# FAL65816_Audio.net
KiCad netlist of a schematic drawn in EAGLE
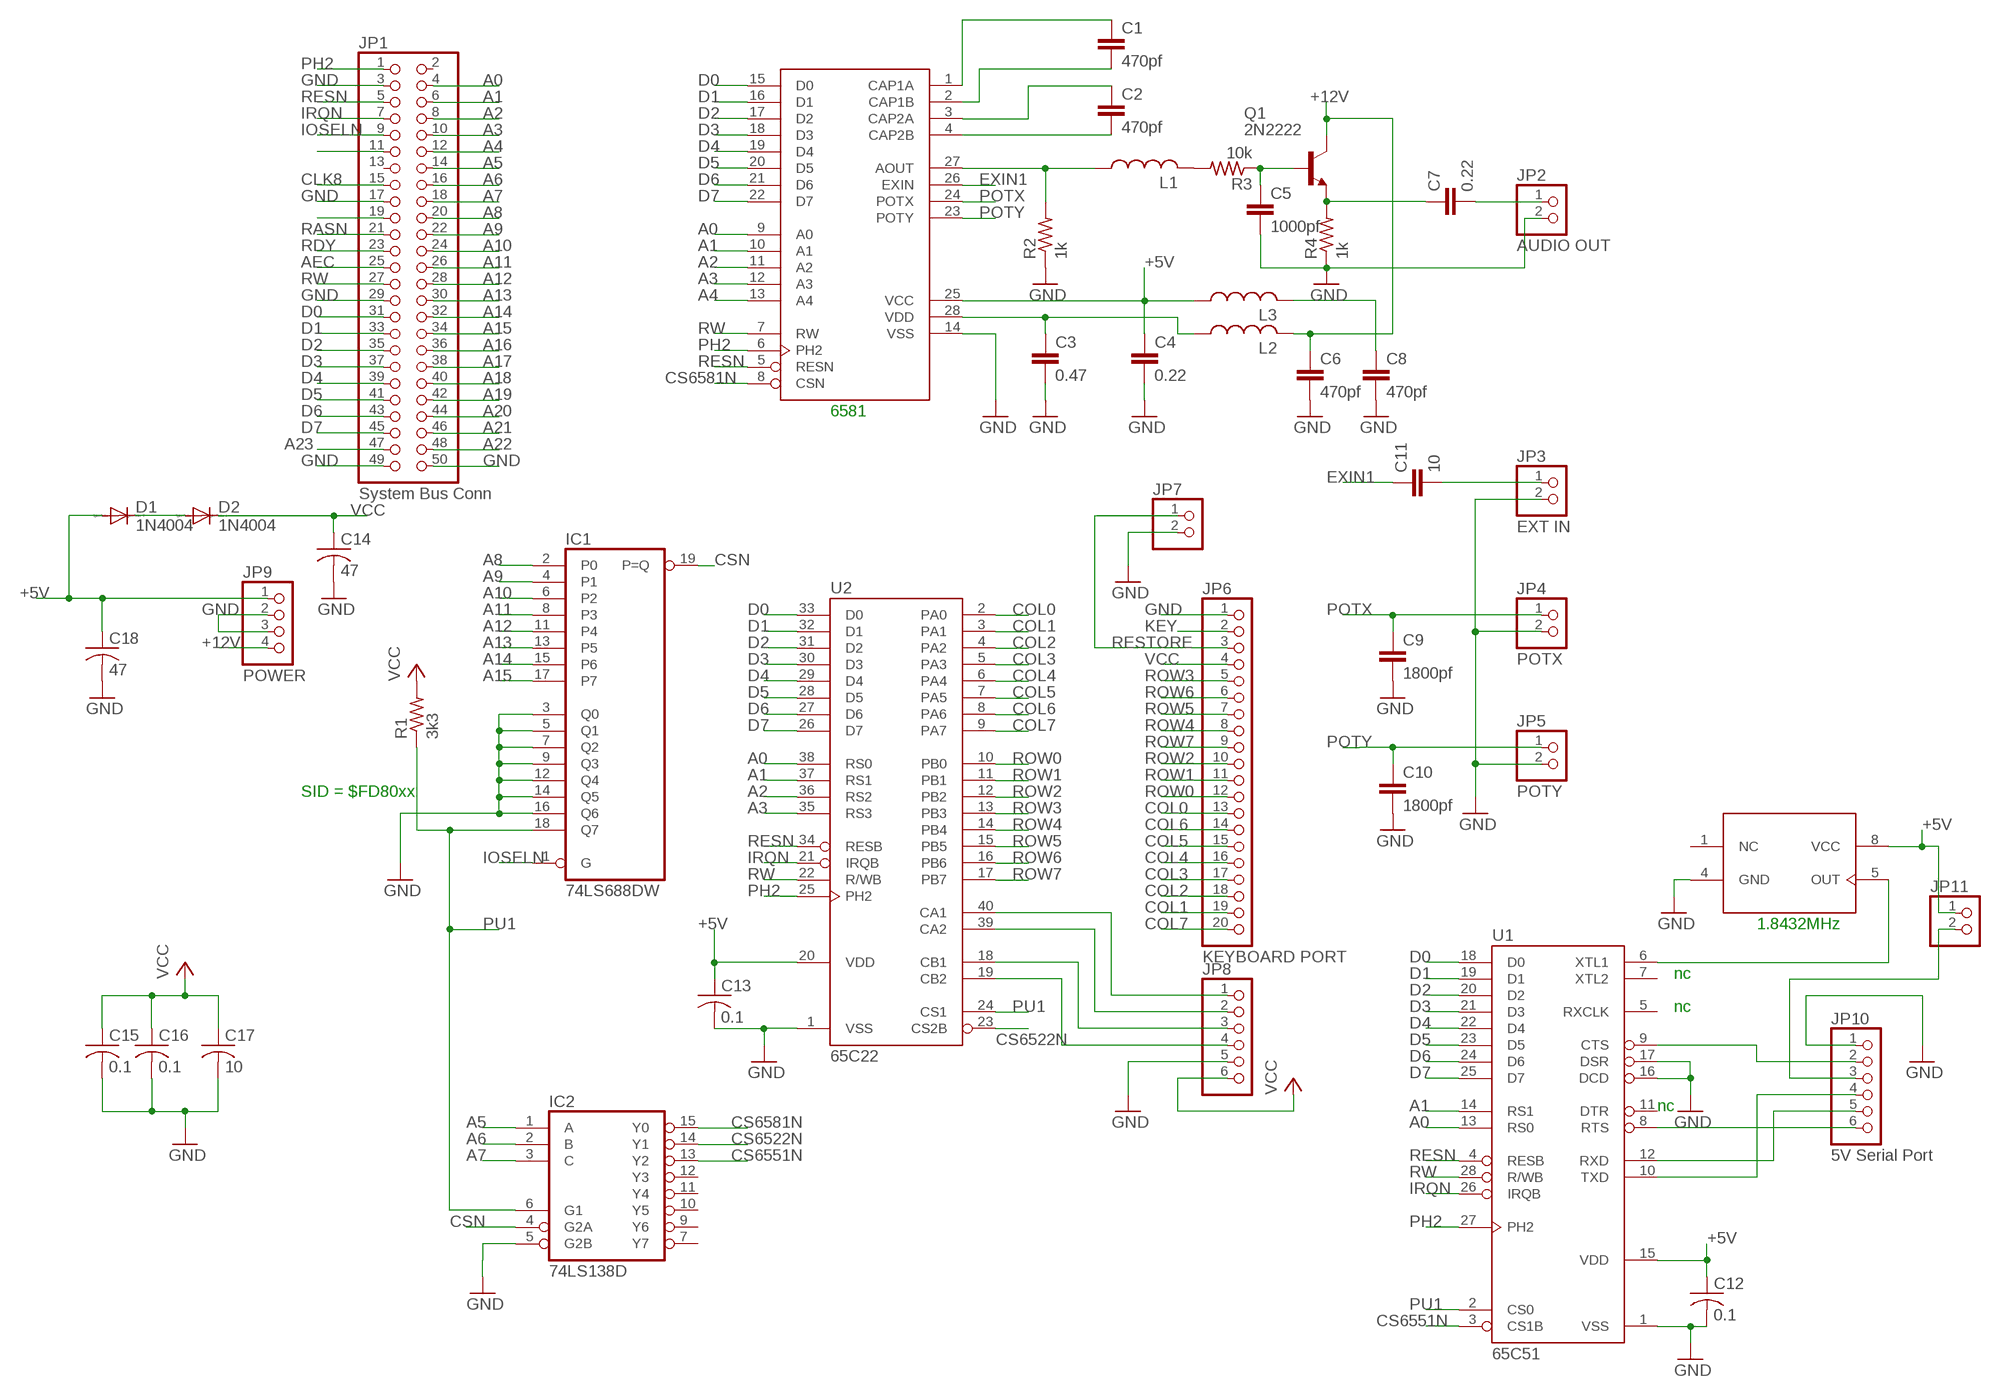
[diagram p0: schematic, sheet 1]

(export (version "E")
  (design (tool "Eeschema 10.0.6"))
  (components
    (comp (ref "C1")
      (value "470pf")
      (footprint "eagle-import:C050-024X044")
      (libsource (lib "eagle-import") (part "C-EU050-024X044"))
    )
    (comp (ref "C2")
      (value "470pf")
      (footprint "eagle-import:C050-024X044")
      (libsource (lib "eagle-import") (part "C-EU050-024X044"))
    )
    (comp (ref "C3")
      (value "0.47")
      (footprint "eagle-import:C050-024X044")
      (libsource (lib "eagle-import") (part "C-EU050-024X044"))
    )
    (comp (ref "C4")
      (value "0.22")
      (footprint "eagle-import:C050-024X044")
      (libsource (lib "eagle-import") (part "C-EU050-024X044"))
    )
    (comp (ref "C5")
      (value "1000pf")
      (footprint "eagle-import:C050-024X044")
      (libsource (lib "eagle-import") (part "C-EU050-024X044"))
    )
    (comp (ref "C6")
      (value "470pf")
      (footprint "eagle-import:C050-024X044")
      (libsource (lib "eagle-import") (part "C-EU050-024X044"))
    )
    (comp (ref "C7")
      (value "0.22")
      (footprint "eagle-import:C050-024X044")
      (libsource (lib "eagle-import") (part "C-EU050-024X044"))
    )
    (comp (ref "C8")
      (value "470pf")
      (footprint "eagle-import:C050-024X044")
      (libsource (lib "eagle-import") (part "C-EU050-024X044"))
    )
    (comp (ref "C9")
      (value "1800pf")
      (footprint "eagle-import:C050-024X044")
      (libsource (lib "eagle-import") (part "C-EU050-024X044"))
    )
    (comp (ref "C10")
      (value "1800pf")
      (footprint "eagle-import:C050-024X044")
      (libsource (lib "eagle-import") (part "C-EU050-024X044"))
    )
    (comp (ref "C11")
      (value "10")
      (footprint "eagle-import:C050-024X044")
      (libsource (lib "eagle-import") (part "C-EU050-024X044"))
    )
    (comp (ref "C12")
      (value "0.1")
      (footprint "eagle-import:C050-024X044")
      (libsource (lib "eagle-import") (part "C-US050-024X044"))
    )
    (comp (ref "C13")
      (value "0.1")
      (footprint "eagle-import:C050-024X044")
      (libsource (lib "eagle-import") (part "C-US050-024X044"))
    )
    (comp (ref "C14")
      (value "47")
      (footprint "eagle-import:C050-024X044")
      (libsource (lib "eagle-import") (part "C-US050-024X044"))
    )
    (comp (ref "C15")
      (value "0.1")
      (footprint "eagle-import:C050-024X044")
      (libsource (lib "eagle-import") (part "C-US050-024X044"))
    )
    (comp (ref "C16")
      (value "0.1")
      (footprint "eagle-import:C050-024X044")
      (libsource (lib "eagle-import") (part "C-US050-024X044"))
    )
    (comp (ref "C17")
      (value "10")
      (footprint "eagle-import:C050-024X044")
      (libsource (lib "eagle-import") (part "C-US050-024X044"))
    )
    (comp (ref "C18")
      (value "47")
      (footprint "eagle-import:C050-024X044")
      (libsource (lib "eagle-import") (part "C-US050-024X044"))
    )
    (comp (ref "D1")
      (value "1N4004")
      (footprint "eagle-import:DO41-10")
      (libsource (lib "eagle-import") (part "1N4004"))
    )
    (comp (ref "D2")
      (value "1N4004")
      (footprint "eagle-import:DO41-10")
      (libsource (lib "eagle-import") (part "1N4004"))
    )
    (comp (ref "IC1")
      (value "74LS688DW")
      (footprint "eagle-import:SO20W")
      (libsource (lib "eagle-import") (part "74688DWLS"))
    )
    (comp (ref "IC2")
      (value "74LS138D")
      (footprint "eagle-import:SO16")
      (libsource (lib "eagle-import") (part "74138DLS"))
    )
    (comp (ref "JP1")
      (value "System Bus Conn")
      (footprint "eagle-import:2X25_90")
      (libsource (lib "eagle-import") (part "PINHD-2X25/90"))
    )
    (comp (ref "JP2")
      (value "AUDIO OUT")
      (footprint "eagle-import:1X02")
      (libsource (lib "eagle-import") (part "PINHD-1X2"))
    )
    (comp (ref "JP3")
      (value "EXT IN")
      (footprint "eagle-import:1X02")
      (libsource (lib "eagle-import") (part "PINHD-1X2"))
    )
    (comp (ref "JP4")
      (value "POTX")
      (footprint "eagle-import:1X02")
      (libsource (lib "eagle-import") (part "PINHD-1X2"))
    )
    (comp (ref "JP5")
      (value "POTY")
      (footprint "eagle-import:1X02")
      (libsource (lib "eagle-import") (part "PINHD-1X2"))
    )
    (comp (ref "JP6")
      (value "KEYBOARD PORT")
      (footprint "eagle-import:1X20")
      (libsource (lib "eagle-import") (part "PINHD-1X20"))
    )
    (comp (ref "JP7")
      (value "PINHD-1X2")
      (footprint "eagle-import:1X02")
      (libsource (lib "eagle-import") (part "PINHD-1X2"))
    )
    (comp (ref "JP8")
      (value "PINHD-1X6/90")
      (footprint "eagle-import:1X06_90")
      (libsource (lib "eagle-import") (part "PINHD-1X6/90"))
    )
    (comp (ref "JP9")
      (value "POWER")
      (footprint "eagle-import:1X04_90")
      (libsource (lib "eagle-import") (part "PINHD-1X4/90"))
    )
    (comp (ref "JP10")
      (value "5V Serial Port")
      (footprint "eagle-import:1X06_90")
      (libsource (lib "eagle-import") (part "PINHD-1X6/90"))
    )
    (comp (ref "JP11")
      (value "PINHD-1X2")
      (footprint "eagle-import:1X02")
      (libsource (lib "eagle-import") (part "PINHD-1X2"))
    )
    (comp (ref "L1")
      (value "L-US0204/7")
      (footprint "eagle-import:0204_7")
      (libsource (lib "eagle-import") (part "L-US0204/7"))
    )
    (comp (ref "L2")
      (value "L-US0204/7")
      (footprint "eagle-import:0204_7")
      (libsource (lib "eagle-import") (part "L-US0204/7"))
    )
    (comp (ref "L3")
      (value "L-US0204/7")
      (footprint "eagle-import:0204_7")
      (libsource (lib "eagle-import") (part "L-US0204/7"))
    )
    (comp (ref "Q1")
      (value "2N2222")
      (footprint "eagle-import:TO18")
      (libsource (lib "eagle-import") (part "2N2222"))
    )
    (comp (ref "R1")
      (value "3k3")
      (footprint "eagle-import:0204_7")
      (libsource (lib "eagle-import") (part "R-US_0204/7"))
    )
    (comp (ref "R2")
      (value "1k")
      (footprint "eagle-import:0204_7")
      (libsource (lib "eagle-import") (part "R-US_0204/7"))
    )
    (comp (ref "R3")
      (value "10k")
      (footprint "eagle-import:0204_7")
      (libsource (lib "eagle-import") (part "R-US_0204/7"))
    )
    (comp (ref "R4")
      (value "1k")
      (footprint "eagle-import:0204_7")
      (libsource (lib "eagle-import") (part "R-US_0204/7"))
    )
    (comp (ref "U$1")
      (value "6581")
      (footprint "eagle-import:DIP-28")
      (libsource (lib "eagle-import") (part "FT6581"))
    )
    (comp (ref "U$2")
      (value "1.8432MHz")
      (footprint "eagle-import:DIL08")
      (libsource (lib "eagle-import") (part "OSC"))
    )
    (comp (ref "U1")
      (value "65C51")
      (footprint "eagle-import:DIP-28")
      (libsource (lib "eagle-import") (part "G65SC51P"))
    )
    (comp (ref "U2")
      (value "65C22")
      (footprint "eagle-import:DIP-40")
      (libsource (lib "eagle-import") (part "G65SC22P"))
    )
  )
  (nets
    (net (code "1") (name "/+5V") (class "Default")
      (node (ref "C12") (pin "1") (pinfunction "1_1") (pintype "passive"))
      (node (ref "C13") (pin "1") (pinfunction "1_1") (pintype "passive"))
      (node (ref "C18") (pin "1") (pinfunction "1_1") (pintype "passive"))
      (node (ref "C4") (pin "1") (pinfunction "1_1") (pintype "passive"))
      (node (ref "D1") (pin "A") (pinfunction "A_A") (pintype "passive"))
      (node (ref "JP11") (pin "1") (pinfunction "1_1") (pintype "passive"))
      (node (ref "JP9") (pin "1") (pinfunction "1_1") (pintype "passive"))
      (node (ref "L3") (pin "1") (pinfunction "1_1") (pintype "passive"))
      (node (ref "U$1") (pin "25") (pinfunction "VCC_25") (pintype "power_in"))
      (node (ref "U$2") (pin "8") (pinfunction "VCC_8") (pintype "power_in"))
      (node (ref "U1") (pin "15") (pinfunction "VDD_15") (pintype "power_in"))
      (node (ref "U2") (pin "20") (pinfunction "VDD_20") (pintype "power_in"))
    )
    (net (code "2") (name "/+12V") (class "Default")
      (node (ref "C6") (pin "1") (pinfunction "1_1") (pintype "passive"))
      (node (ref "JP9") (pin "4") (pinfunction "4_4") (pintype "passive"))
      (node (ref "L2") (pin "2") (pinfunction "2_2") (pintype "passive"))
      (node (ref "Q1") (pin "3") (pinfunction "C_3") (pintype "passive"))
    )
    (net (code "3") (name "/A0") (class "Default")
      (node (ref "JP1") (pin "4") (pinfunction "4_4") (pintype "passive"))
      (node (ref "U$1") (pin "9") (pinfunction "A0_9") (pintype "input"))
      (node (ref "U1") (pin "13") (pinfunction "RS0_13") (pintype "input"))
      (node (ref "U2") (pin "38") (pinfunction "RS0_38") (pintype "input"))
    )
    (net (code "4") (name "/A1") (class "Default")
      (node (ref "JP1") (pin "6") (pinfunction "6_6") (pintype "passive"))
      (node (ref "U$1") (pin "10") (pinfunction "A1_10") (pintype "input"))
      (node (ref "U1") (pin "14") (pinfunction "RS1_14") (pintype "input"))
      (node (ref "U2") (pin "37") (pinfunction "RS1_37") (pintype "input"))
    )
    (net (code "5") (name "/A2") (class "Default")
      (node (ref "JP1") (pin "8") (pinfunction "8_8") (pintype "passive"))
      (node (ref "U$1") (pin "11") (pinfunction "A2_11") (pintype "input"))
      (node (ref "U2") (pin "36") (pinfunction "RS2_36") (pintype "input"))
    )
    (net (code "6") (name "/A3") (class "Default")
      (node (ref "JP1") (pin "10") (pinfunction "10_10") (pintype "passive"))
      (node (ref "U$1") (pin "12") (pinfunction "A3_12") (pintype "input"))
      (node (ref "U2") (pin "35") (pinfunction "RS3_35") (pintype "input"))
    )
    (net (code "7") (name "/A4") (class "Default")
      (node (ref "JP1") (pin "12") (pinfunction "12_12") (pintype "passive"))
      (node (ref "U$1") (pin "13") (pinfunction "A4_13") (pintype "input"))
    )
    (net (code "8") (name "/A5") (class "Default")
      (node (ref "IC2") (pin "1") (pinfunction "A_1") (pintype "input"))
      (node (ref "JP1") (pin "14") (pinfunction "14_14") (pintype "passive"))
    )
    (net (code "9") (name "/A6") (class "Default")
      (node (ref "IC2") (pin "2") (pinfunction "B_2") (pintype "input"))
      (node (ref "JP1") (pin "16") (pinfunction "16_16") (pintype "passive"))
    )
    (net (code "10") (name "/A7") (class "Default")
      (node (ref "IC2") (pin "3") (pinfunction "C_3") (pintype "input"))
      (node (ref "JP1") (pin "18") (pinfunction "18_18") (pintype "passive"))
    )
    (net (code "11") (name "/A8") (class "Default")
      (node (ref "IC1") (pin "2") (pinfunction "P0_2") (pintype "input"))
      (node (ref "JP1") (pin "20") (pinfunction "20_20") (pintype "passive"))
    )
    (net (code "12") (name "/A9") (class "Default")
      (node (ref "IC1") (pin "4") (pinfunction "P1_4") (pintype "input"))
      (node (ref "JP1") (pin "22") (pinfunction "22_22") (pintype "passive"))
    )
    (net (code "13") (name "/A10") (class "Default")
      (node (ref "IC1") (pin "6") (pinfunction "P2_6") (pintype "input"))
      (node (ref "JP1") (pin "24") (pinfunction "24_24") (pintype "passive"))
    )
    (net (code "14") (name "/A11") (class "Default")
      (node (ref "IC1") (pin "8") (pinfunction "P3_8") (pintype "input"))
      (node (ref "JP1") (pin "26") (pinfunction "26_26") (pintype "passive"))
    )
    (net (code "15") (name "/A12") (class "Default")
      (node (ref "IC1") (pin "11") (pinfunction "P4_11") (pintype "input"))
      (node (ref "JP1") (pin "28") (pinfunction "28_28") (pintype "passive"))
    )
    (net (code "16") (name "/A13") (class "Default")
      (node (ref "IC1") (pin "13") (pinfunction "P5_13") (pintype "input"))
      (node (ref "JP1") (pin "30") (pinfunction "30_30") (pintype "passive"))
    )
    (net (code "17") (name "/A14") (class "Default")
      (node (ref "IC1") (pin "15") (pinfunction "P6_15") (pintype "input"))
      (node (ref "JP1") (pin "32") (pinfunction "32_32") (pintype "passive"))
    )
    (net (code "18") (name "/A15") (class "Default")
      (node (ref "IC1") (pin "17") (pinfunction "P7_17") (pintype "input"))
      (node (ref "JP1") (pin "34") (pinfunction "34_34") (pintype "passive"))
    )
    (net (code "19") (name "/A16") (class "Default")
      (node (ref "JP1") (pin "36") (pinfunction "36_36") (pintype "passive"))
    )
    (net (code "20") (name "/A17") (class "Default")
      (node (ref "JP1") (pin "38") (pinfunction "38_38") (pintype "passive"))
    )
    (net (code "21") (name "/A18") (class "Default")
      (node (ref "JP1") (pin "40") (pinfunction "40_40") (pintype "passive"))
    )
    (net (code "22") (name "/A19") (class "Default")
      (node (ref "JP1") (pin "42") (pinfunction "42_42") (pintype "passive"))
    )
    (net (code "23") (name "/A20") (class "Default")
      (node (ref "JP1") (pin "44") (pinfunction "44_44") (pintype "passive"))
    )
    (net (code "24") (name "/A21") (class "Default")
      (node (ref "JP1") (pin "46") (pinfunction "46_46") (pintype "passive"))
    )
    (net (code "25") (name "/A22") (class "Default")
      (node (ref "JP1") (pin "48") (pinfunction "48_48") (pintype "passive"))
    )
    (net (code "26") (name "/A23") (class "Default")
      (node (ref "JP1") (pin "47") (pinfunction "47_47") (pintype "passive"))
    )
    (net (code "27") (name "/AEC") (class "Default")
      (node (ref "JP1") (pin "25") (pinfunction "25_25") (pintype "passive"))
    )
    (net (code "28") (name "/CLK8") (class "Default")
      (node (ref "JP1") (pin "15") (pinfunction "15_15") (pintype "passive"))
    )
    (net (code "29") (name "/COL0") (class "Default")
      (node (ref "JP6") (pin "13") (pinfunction "13_13") (pintype "passive"))
      (node (ref "U2") (pin "2") (pinfunction "PA0_2") (pintype "bidirectional"))
    )
    (net (code "30") (name "/COL1") (class "Default")
      (node (ref "JP6") (pin "19") (pinfunction "19_19") (pintype "passive"))
      (node (ref "U2") (pin "3") (pinfunction "PA1_3") (pintype "bidirectional"))
    )
    (net (code "31") (name "/COL2") (class "Default")
      (node (ref "JP6") (pin "18") (pinfunction "18_18") (pintype "passive"))
      (node (ref "U2") (pin "4") (pinfunction "PA2_4") (pintype "bidirectional"))
    )
    (net (code "32") (name "/COL3") (class "Default")
      (node (ref "JP6") (pin "17") (pinfunction "17_17") (pintype "passive"))
      (node (ref "U2") (pin "5") (pinfunction "PA3_5") (pintype "bidirectional"))
    )
    (net (code "33") (name "/COL4") (class "Default")
      (node (ref "JP6") (pin "16") (pinfunction "16_16") (pintype "passive"))
      (node (ref "U2") (pin "6") (pinfunction "PA4_6") (pintype "bidirectional"))
    )
    (net (code "34") (name "/COL5") (class "Default")
      (node (ref "JP6") (pin "15") (pinfunction "15_15") (pintype "passive"))
      (node (ref "U2") (pin "7") (pinfunction "PA5_7") (pintype "bidirectional"))
    )
    (net (code "35") (name "/COL6") (class "Default")
      (node (ref "JP6") (pin "14") (pinfunction "14_14") (pintype "passive"))
      (node (ref "U2") (pin "8") (pinfunction "PA6_8") (pintype "bidirectional"))
    )
    (net (code "36") (name "/COL7") (class "Default")
      (node (ref "JP6") (pin "20") (pinfunction "20_20") (pintype "passive"))
      (node (ref "U2") (pin "9") (pinfunction "PA7_9") (pintype "bidirectional"))
    )
    (net (code "37") (name "/CS6522N") (class "Default")
      (node (ref "IC2") (pin "14") (pinfunction "Y1_14") (pintype "output"))
      (node (ref "U2") (pin "23") (pinfunction "CS2B_23") (pintype "input"))
    )
    (net (code "38") (name "/CS6551N") (class "Default")
      (node (ref "IC2") (pin "13") (pinfunction "Y2_13") (pintype "output"))
      (node (ref "U1") (pin "3") (pinfunction "CS1B_3") (pintype "input"))
    )
    (net (code "39") (name "/CS6581N") (class "Default")
      (node (ref "IC2") (pin "15") (pinfunction "Y0_15") (pintype "output"))
      (node (ref "U$1") (pin "8") (pinfunction "CSN_8") (pintype "input"))
    )
    (net (code "40") (name "/CSN") (class "Default")
      (node (ref "IC1") (pin "19") (pinfunction "P=Q_19") (pintype "output"))
      (node (ref "IC2") (pin "4") (pinfunction "G2A_4") (pintype "input"))
    )
    (net (code "41") (name "/D0") (class "Default")
      (node (ref "JP1") (pin "31") (pinfunction "31_31") (pintype "passive"))
      (node (ref "U$1") (pin "15") (pinfunction "D0_15") (pintype "bidirectional"))
      (node (ref "U1") (pin "18") (pinfunction "D0_18") (pintype "bidirectional"))
      (node (ref "U2") (pin "33") (pinfunction "D0_33") (pintype "bidirectional"))
    )
    (net (code "42") (name "/D1") (class "Default")
      (node (ref "JP1") (pin "33") (pinfunction "33_33") (pintype "passive"))
      (node (ref "U$1") (pin "16") (pinfunction "D1_16") (pintype "bidirectional"))
      (node (ref "U1") (pin "19") (pinfunction "D1_19") (pintype "bidirectional"))
      (node (ref "U2") (pin "32") (pinfunction "D1_32") (pintype "bidirectional"))
    )
    (net (code "43") (name "/D2") (class "Default")
      (node (ref "JP1") (pin "35") (pinfunction "35_35") (pintype "passive"))
      (node (ref "U$1") (pin "17") (pinfunction "D2_17") (pintype "bidirectional"))
      (node (ref "U1") (pin "20") (pinfunction "D2_20") (pintype "bidirectional"))
      (node (ref "U2") (pin "31") (pinfunction "D2_31") (pintype "bidirectional"))
    )
    (net (code "44") (name "/D3") (class "Default")
      (node (ref "JP1") (pin "37") (pinfunction "37_37") (pintype "passive"))
      (node (ref "U$1") (pin "18") (pinfunction "D3_18") (pintype "bidirectional"))
      (node (ref "U1") (pin "21") (pinfunction "D3_21") (pintype "bidirectional"))
      (node (ref "U2") (pin "30") (pinfunction "D3_30") (pintype "bidirectional"))
    )
    (net (code "45") (name "/D4") (class "Default")
      (node (ref "JP1") (pin "39") (pinfunction "39_39") (pintype "passive"))
      (node (ref "U$1") (pin "19") (pinfunction "D4_19") (pintype "bidirectional"))
      (node (ref "U1") (pin "22") (pinfunction "D4_22") (pintype "bidirectional"))
      (node (ref "U2") (pin "29") (pinfunction "D4_29") (pintype "bidirectional"))
    )
    (net (code "46") (name "/D5") (class "Default")
      (node (ref "JP1") (pin "41") (pinfunction "41_41") (pintype "passive"))
      (node (ref "U$1") (pin "20") (pinfunction "D5_20") (pintype "bidirectional"))
      (node (ref "U1") (pin "23") (pinfunction "D5_23") (pintype "bidirectional"))
      (node (ref "U2") (pin "28") (pinfunction "D5_28") (pintype "bidirectional"))
    )
    (net (code "47") (name "/D6") (class "Default")
      (node (ref "JP1") (pin "43") (pinfunction "43_43") (pintype "passive"))
      (node (ref "U$1") (pin "21") (pinfunction "D6_21") (pintype "bidirectional"))
      (node (ref "U1") (pin "24") (pinfunction "D6_24") (pintype "bidirectional"))
      (node (ref "U2") (pin "27") (pinfunction "D6_27") (pintype "bidirectional"))
    )
    (net (code "48") (name "/D7") (class "Default")
      (node (ref "JP1") (pin "45") (pinfunction "45_45") (pintype "passive"))
      (node (ref "U$1") (pin "22") (pinfunction "D7_22") (pintype "bidirectional"))
      (node (ref "U1") (pin "25") (pinfunction "D7_25") (pintype "bidirectional"))
      (node (ref "U2") (pin "26") (pinfunction "D7_26") (pintype "bidirectional"))
    )
    (net (code "49") (name "/EXIN1") (class "Default")
      (node (ref "C11") (pin "1") (pinfunction "1_1") (pintype "passive"))
      (node (ref "U$1") (pin "26") (pinfunction "EXIN_26") (pintype "input"))
    )
    (net (code "50") (name "/IOSELN") (class "Default")
      (node (ref "IC1") (pin "1") (pinfunction "G_1") (pintype "input"))
      (node (ref "JP1") (pin "9") (pinfunction "9_9") (pintype "passive"))
    )
    (net (code "51") (name "/IRQN") (class "Default")
      (node (ref "JP1") (pin "7") (pinfunction "7_7") (pintype "passive"))
      (node (ref "U1") (pin "26") (pinfunction "IRQB_26") (pintype "output"))
      (node (ref "U2") (pin "21") (pinfunction "IRQB_21") (pintype "output"))
    )
    (net (code "52") (name "/KEY") (class "Default")
      (node (ref "JP6") (pin "2") (pinfunction "2_2") (pintype "passive"))
    )
    (net (code "53") (name "/PH2") (class "Default")
      (node (ref "JP1") (pin "1") (pinfunction "1_1") (pintype "passive"))
      (node (ref "U$1") (pin "6") (pinfunction "PH2_6") (pintype "input"))
      (node (ref "U1") (pin "27") (pinfunction "PH2_27") (pintype "power_in"))
      (node (ref "U2") (pin "25") (pinfunction "PH2_25") (pintype "input"))
    )
    (net (code "54") (name "/POTX") (class "Default")
      (node (ref "C9") (pin "1") (pinfunction "1_1") (pintype "passive"))
      (node (ref "JP4") (pin "1") (pinfunction "1_1") (pintype "passive"))
      (node (ref "U$1") (pin "24") (pinfunction "POTX_24") (pintype "input"))
    )
    (net (code "55") (name "/POTY") (class "Default")
      (node (ref "C10") (pin "1") (pinfunction "1_1") (pintype "passive"))
      (node (ref "JP5") (pin "1") (pinfunction "1_1") (pintype "passive"))
      (node (ref "U$1") (pin "23") (pinfunction "POTY_23") (pintype "input"))
    )
    (net (code "56") (name "/PU1") (class "Default")
      (node (ref "IC1") (pin "18") (pinfunction "Q7_18") (pintype "input"))
      (node (ref "IC2") (pin "6") (pinfunction "G1_6") (pintype "input"))
      (node (ref "R1") (pin "1") (pinfunction "1_1") (pintype "passive"))
      (node (ref "U1") (pin "2") (pinfunction "CS0_2") (pintype "input"))
      (node (ref "U2") (pin "24") (pinfunction "CS1_24") (pintype "input"))
    )
    (net (code "57") (name "/RASN") (class "Default")
      (node (ref "JP1") (pin "21") (pinfunction "21_21") (pintype "passive"))
    )
    (net (code "58") (name "/RDY") (class "Default")
      (node (ref "JP1") (pin "23") (pinfunction "23_23") (pintype "passive"))
    )
    (net (code "59") (name "/RESN") (class "Default")
      (node (ref "JP1") (pin "5") (pinfunction "5_5") (pintype "passive"))
      (node (ref "U$1") (pin "5") (pinfunction "RESN_5") (pintype "input"))
      (node (ref "U1") (pin "4") (pinfunction "RESB_4") (pintype "input"))
      (node (ref "U2") (pin "34") (pinfunction "RESB_34") (pintype "input"))
    )
    (net (code "60") (name "/RESTORE") (class "Default")
      (node (ref "JP6") (pin "3") (pinfunction "3_3") (pintype "passive"))
      (node (ref "JP7") (pin "1") (pinfunction "1_1") (pintype "passive"))
    )
    (net (code "61") (name "/ROW0") (class "Default")
      (node (ref "JP6") (pin "12") (pinfunction "12_12") (pintype "passive"))
      (node (ref "U2") (pin "10") (pinfunction "PB0_10") (pintype "bidirectional"))
    )
    (net (code "62") (name "/ROW1") (class "Default")
      (node (ref "JP6") (pin "11") (pinfunction "11_11") (pintype "passive"))
      (node (ref "U2") (pin "11") (pinfunction "PB1_11") (pintype "bidirectional"))
    )
    (net (code "63") (name "/ROW2") (class "Default")
      (node (ref "JP6") (pin "10") (pinfunction "10_10") (pintype "passive"))
      (node (ref "U2") (pin "12") (pinfunction "PB2_12") (pintype "bidirectional"))
    )
    (net (code "64") (name "/ROW3") (class "Default")
      (node (ref "JP6") (pin "5") (pinfunction "5_5") (pintype "passive"))
      (node (ref "U2") (pin "13") (pinfunction "PB3_13") (pintype "bidirectional"))
    )
    (net (code "65") (name "/ROW4") (class "Default")
      (node (ref "JP6") (pin "8") (pinfunction "8_8") (pintype "passive"))
      (node (ref "U2") (pin "14") (pinfunction "PB4_14") (pintype "bidirectional"))
    )
    (net (code "66") (name "/ROW5") (class "Default")
      (node (ref "JP6") (pin "7") (pinfunction "7_7") (pintype "passive"))
      (node (ref "U2") (pin "15") (pinfunction "PB5_15") (pintype "bidirectional"))
    )
    (net (code "67") (name "/ROW6") (class "Default")
      (node (ref "JP6") (pin "6") (pinfunction "6_6") (pintype "passive"))
      (node (ref "U2") (pin "16") (pinfunction "PB6_16") (pintype "bidirectional"))
    )
    (net (code "68") (name "/ROW7") (class "Default")
      (node (ref "JP6") (pin "9") (pinfunction "9_9") (pintype "passive"))
      (node (ref "U2") (pin "17") (pinfunction "PB7_17") (pintype "bidirectional"))
    )
    (net (code "69") (name "/RW") (class "Default")
      (node (ref "JP1") (pin "27") (pinfunction "27_27") (pintype "passive"))
      (node (ref "U$1") (pin "7") (pinfunction "RW_7") (pintype "input"))
      (node (ref "U1") (pin "28") (pinfunction "R/WB_28") (pintype "input"))
      (node (ref "U2") (pin "22") (pinfunction "R/WB_22") (pintype "input"))
    )
    (net (code "70") (name "GND") (class "Default")
      (node (ref "C10") (pin "2") (pinfunction "2_2") (pintype "passive"))
      (node (ref "C12") (pin "2") (pinfunction "2_2") (pintype "passive"))
      (node (ref "C13") (pin "2") (pinfunction "2_2") (pintype "passive"))
      (node (ref "C14") (pin "2") (pinfunction "2_2") (pintype "passive"))
      (node (ref "C15") (pin "2") (pinfunction "2_2") (pintype "passive"))
      (node (ref "C16") (pin "2") (pinfunction "2_2") (pintype "passive"))
      (node (ref "C17") (pin "2") (pinfunction "2_2") (pintype "passive"))
      (node (ref "C18") (pin "2") (pinfunction "2_2") (pintype "passive"))
      (node (ref "C3") (pin "2") (pinfunction "2_2") (pintype "passive"))
      (node (ref "C4") (pin "2") (pinfunction "2_2") (pintype "passive"))
      (node (ref "C5") (pin "2") (pinfunction "2_2") (pintype "passive"))
      (node (ref "C6") (pin "2") (pinfunction "2_2") (pintype "passive"))
      (node (ref "C8") (pin "2") (pinfunction "2_2") (pintype "passive"))
      (node (ref "C9") (pin "2") (pinfunction "2_2") (pintype "passive"))
      (node (ref "IC1") (pin "12") (pinfunction "Q4_12") (pintype "input"))
      (node (ref "IC1") (pin "14") (pinfunction "Q5_14") (pintype "input"))
      (node (ref "IC1") (pin "16") (pinfunction "Q6_16") (pintype "input"))
      (node (ref "IC1") (pin "3") (pinfunction "Q0_3") (pintype "input"))
      (node (ref "IC1") (pin "5") (pinfunction "Q1_5") (pintype "input"))
      (node (ref "IC1") (pin "7") (pinfunction "Q2_7") (pintype "input"))
      (node (ref "IC1") (pin "9") (pinfunction "Q3_9") (pintype "input"))
      (node (ref "IC2") (pin "5") (pinfunction "G2B_5") (pintype "input"))
      (node (ref "JP1") (pin "17") (pinfunction "17_17") (pintype "passive"))
      (node (ref "JP1") (pin "29") (pinfunction "29_29") (pintype "passive"))
      (node (ref "JP1") (pin "3") (pinfunction "3_3") (pintype "passive"))
      (node (ref "JP1") (pin "49") (pinfunction "49_49") (pintype "passive"))
      (node (ref "JP1") (pin "50") (pinfunction "50_50") (pintype "passive"))
      (node (ref "JP10") (pin "1") (pinfunction "1_1") (pintype "passive"))
      (node (ref "JP2") (pin "2") (pinfunction "2_2") (pintype "passive"))
      (node (ref "JP3") (pin "2") (pinfunction "2_2") (pintype "passive"))
      (node (ref "JP4") (pin "2") (pinfunction "2_2") (pintype "passive"))
      (node (ref "JP5") (pin "2") (pinfunction "2_2") (pintype "passive"))
      (node (ref "JP6") (pin "1") (pinfunction "1_1") (pintype "passive"))
      (node (ref "JP7") (pin "2") (pinfunction "2_2") (pintype "passive"))
      (node (ref "JP8") (pin "5") (pinfunction "5_5") (pintype "passive"))
      (node (ref "JP9") (pin "2") (pinfunction "2_2") (pintype "passive"))
      (node (ref "JP9") (pin "3") (pinfunction "3_3") (pintype "passive"))
      (node (ref "R2") (pin "1") (pinfunction "1_1") (pintype "passive"))
      (node (ref "R4") (pin "1") (pinfunction "1_1") (pintype "passive"))
      (node (ref "U$1") (pin "14") (pinfunction "VSS_14") (pintype "power_in"))
      (node (ref "U$2") (pin "4") (pinfunction "GND_4") (pintype "power_in"))
      (node (ref "U1") (pin "1") (pinfunction "VSS_1") (pintype "power_in"))
      (node (ref "U1") (pin "16") (pinfunction "DCD_16") (pintype "input"))
      (node (ref "U1") (pin "17") (pinfunction "DSR_17") (pintype "input"))
      (node (ref "U2") (pin "1") (pinfunction "VSS_1") (pintype "power_in"))
    )
    (net (code "71") (name "Net-(C7-Pad2)") (class "Default")
      (node (ref "C7") (pin "2") (pinfunction "2_2") (pintype "passive"))
      (node (ref "JP2") (pin "1") (pinfunction "1_1") (pintype "passive"))
    )
    (net (code "72") (name "Net-(C8-Pad1)") (class "Default")
      (node (ref "C8") (pin "1") (pinfunction "1_1") (pintype "passive"))
      (node (ref "L3") (pin "2") (pinfunction "2_2") (pintype "passive"))
    )
    (net (code "73") (name "Net-(C11-Pad2)") (class "Default")
      (node (ref "C11") (pin "2") (pinfunction "2_2") (pintype "passive"))
      (node (ref "JP3") (pin "1") (pinfunction "1_1") (pintype "passive"))
    )
    (net (code "74") (name "Net-(D1-PadC)") (class "Default")
      (node (ref "D1") (pin "C") (pinfunction "C_C") (pintype "passive"))
      (node (ref "D2") (pin "A") (pinfunction "A_A") (pintype "passive"))
    )
    (net (code "75") (name "Net-(JP10-Pad3)") (class "Default")
      (node (ref "JP10") (pin "3") (pinfunction "3_3") (pintype "passive"))
      (node (ref "JP11") (pin "2") (pinfunction "2_2") (pintype "passive"))
    )
    (net (code "76") (name "Net-(L1-Pad2)") (class "Default")
      (node (ref "L1") (pin "2") (pinfunction "2_2") (pintype "passive"))
      (node (ref "R3") (pin "2") (pinfunction "2_2") (pintype "passive"))
    )
    (net (code "77") (name "Net-(Q1-B)") (class "Default")
      (node (ref "C5") (pin "1") (pinfunction "1_1") (pintype "passive"))
      (node (ref "Q1") (pin "2") (pinfunction "B_2") (pintype "passive"))
      (node (ref "R3") (pin "1") (pinfunction "1_1") (pintype "passive"))
    )
    (net (code "78") (name "Net-(Q1-E)") (class "Default")
      (node (ref "C7") (pin "1") (pinfunction "1_1") (pintype "passive"))
      (node (ref "Q1") (pin "1") (pinfunction "E_1") (pintype "passive"))
      (node (ref "R4") (pin "2") (pinfunction "2_2") (pintype "passive"))
    )
    (net (code "79") (name "Net-(U$1-AOUT)") (class "Default")
      (node (ref "L1") (pin "1") (pinfunction "1_1") (pintype "passive"))
      (node (ref "R2") (pin "2") (pinfunction "2_2") (pintype "passive"))
      (node (ref "U$1") (pin "27") (pinfunction "AOUT_27") (pintype "output"))
    )
    (net (code "80") (name "Net-(U$1-CAP1A)") (class "Default")
      (node (ref "C1") (pin "1") (pinfunction "1_1") (pintype "passive"))
      (node (ref "U$1") (pin "1") (pinfunction "CAP1A_1") (pintype "bidirectional"))
    )
    (net (code "81") (name "Net-(U$1-CAP1B)") (class "Default")
      (node (ref "C1") (pin "2") (pinfunction "2_2") (pintype "passive"))
      (node (ref "U$1") (pin "2") (pinfunction "CAP1B_2") (pintype "bidirectional"))
    )
    (net (code "82") (name "Net-(U$1-CAP2A)") (class "Default")
      (node (ref "C2") (pin "1") (pinfunction "1_1") (pintype "passive"))
      (node (ref "U$1") (pin "3") (pinfunction "CAP2A_3") (pintype "bidirectional"))
    )
    (net (code "83") (name "Net-(U$1-CAP2B)") (class "Default")
      (node (ref "C2") (pin "2") (pinfunction "2_2") (pintype "passive"))
      (node (ref "U$1") (pin "4") (pinfunction "CAP2B_4") (pintype "bidirectional"))
    )
    (net (code "84") (name "Net-(U$1-VDD)") (class "Default")
      (node (ref "C3") (pin "1") (pinfunction "1_1") (pintype "passive"))
      (node (ref "L2") (pin "1") (pinfunction "1_1") (pintype "passive"))
      (node (ref "U$1") (pin "28") (pinfunction "VDD_28") (pintype "power_in"))
    )
    (net (code "85") (name "Net-(U$2-OUT)") (class "Default")
      (node (ref "U$2") (pin "5") (pinfunction "OUT_5") (pintype "output"))
      (node (ref "U1") (pin "6") (pinfunction "XTL1_6") (pintype "input"))
    )
    (net (code "86") (name "Net-(U1-CTS)") (class "Default")
      (node (ref "JP10") (pin "2") (pinfunction "2_2") (pintype "passive"))
      (node (ref "U1") (pin "9") (pinfunction "CTS_9") (pintype "input"))
    )
    (net (code "87") (name "Net-(U1-RTS)") (class "Default")
      (node (ref "JP10") (pin "6") (pinfunction "6_6") (pintype "passive"))
      (node (ref "U1") (pin "8") (pinfunction "RTS_8") (pintype "output"))
    )
    (net (code "88") (name "Net-(U1-RXD)") (class "Default")
      (node (ref "JP10") (pin "5") (pinfunction "5_5") (pintype "passive"))
      (node (ref "U1") (pin "12") (pinfunction "RXD_12") (pintype "input"))
    )
    (net (code "89") (name "Net-(U1-TXD)") (class "Default")
      (node (ref "JP10") (pin "4") (pinfunction "4_4") (pintype "passive"))
      (node (ref "U1") (pin "10") (pinfunction "TXD_10") (pintype "output"))
    )
    (net (code "90") (name "Net-(U2-CA1)") (class "Default")
      (node (ref "JP8") (pin "1") (pinfunction "1_1") (pintype "passive"))
      (node (ref "U2") (pin "40") (pinfunction "CA1_40") (pintype "bidirectional"))
    )
    (net (code "91") (name "Net-(U2-CA2)") (class "Default")
      (node (ref "JP8") (pin "2") (pinfunction "2_2") (pintype "passive"))
      (node (ref "U2") (pin "39") (pinfunction "CA2_39") (pintype "bidirectional"))
    )
    (net (code "92") (name "Net-(U2-CB1)") (class "Default")
      (node (ref "JP8") (pin "3") (pinfunction "3_3") (pintype "passive"))
      (node (ref "U2") (pin "18") (pinfunction "CB1_18") (pintype "bidirectional"))
    )
    (net (code "93") (name "Net-(U2-CB2)") (class "Default")
      (node (ref "JP8") (pin "4") (pinfunction "4_4") (pintype "passive"))
      (node (ref "U2") (pin "19") (pinfunction "CB2_19") (pintype "bidirectional"))
    )
    (net (code "94") (name "VCC") (class "Default")
      (node (ref "C14") (pin "1") (pinfunction "1_1") (pintype "passive"))
      (node (ref "C15") (pin "1") (pinfunction "1_1") (pintype "passive"))
      (node (ref "C16") (pin "1") (pinfunction "1_1") (pintype "passive"))
      (node (ref "C17") (pin "1") (pinfunction "1_1") (pintype "passive"))
      (node (ref "D2") (pin "C") (pinfunction "C_C") (pintype "passive"))
      (node (ref "JP6") (pin "4") (pinfunction "4_4") (pintype "passive"))
      (node (ref "JP8") (pin "6") (pinfunction "6_6") (pintype "passive"))
      (node (ref "R1") (pin "2") (pinfunction "2_2") (pintype "passive"))
    )
    (net (code "95") (name "unconnected-(IC2A-Y3-Pad12)") (class "Default")
      (node (ref "IC2") (pin "12") (pinfunction "Y3_12") (pintype "output"))
    )
    (net (code "96") (name "unconnected-(IC2A-Y4-Pad11)") (class "Default")
      (node (ref "IC2") (pin "11") (pinfunction "Y4_11") (pintype "output"))
    )
    (net (code "97") (name "unconnected-(IC2A-Y5-Pad10)") (class "Default")
      (node (ref "IC2") (pin "10") (pinfunction "Y5_10") (pintype "output"))
    )
    (net (code "98") (name "unconnected-(IC2A-Y6-Pad9)") (class "Default")
      (node (ref "IC2") (pin "9") (pinfunction "Y6_9") (pintype "output"))
    )
    (net (code "99") (name "unconnected-(IC2A-Y7-Pad7)") (class "Default")
      (node (ref "IC2") (pin "7") (pinfunction "Y7_7") (pintype "output"))
    )
    (net (code "100") (name "unconnected-(JP1-Pad2)") (class "Default")
      (node (ref "JP1") (pin "2") (pinfunction "2_2") (pintype "passive"))
    )
    (net (code "101") (name "unconnected-(JP1-Pad11)") (class "Default")
      (node (ref "JP1") (pin "11") (pinfunction "11_11") (pintype "passive"))
    )
    (net (code "102") (name "unconnected-(JP1-Pad13)") (class "Default")
      (node (ref "JP1") (pin "13") (pinfunction "13_13") (pintype "passive"))
    )
    (net (code "103") (name "unconnected-(JP1-Pad19)") (class "Default")
      (node (ref "JP1") (pin "19") (pinfunction "19_19") (pintype "passive"))
    )
    (net (code "104") (name "unconnected-(U$2-NC-Pad1)") (class "Default")
      (node (ref "U$2") (pin "1") (pinfunction "NC_1") (pintype "bidirectional"))
    )
    (net (code "105") (name "unconnected-(U1-DTR-Pad11)") (class "Default")
      (node (ref "U1") (pin "11") (pinfunction "DTR_11") (pintype "output"))
    )
    (net (code "106") (name "unconnected-(U1-RXCLK-Pad5)") (class "Default")
      (node (ref "U1") (pin "5") (pinfunction "RXCLK_5") (pintype "bidirectional"))
    )
    (net (code "107") (name "unconnected-(U1-XTL2-Pad7)") (class "Default")
      (node (ref "U1") (pin "7") (pinfunction "XTL2_7") (pintype "output"))
    )
  )
)
